# Chip_Socket_Programmer-X01.net
KiCad netlist of a schematic drawn in Altium Designer
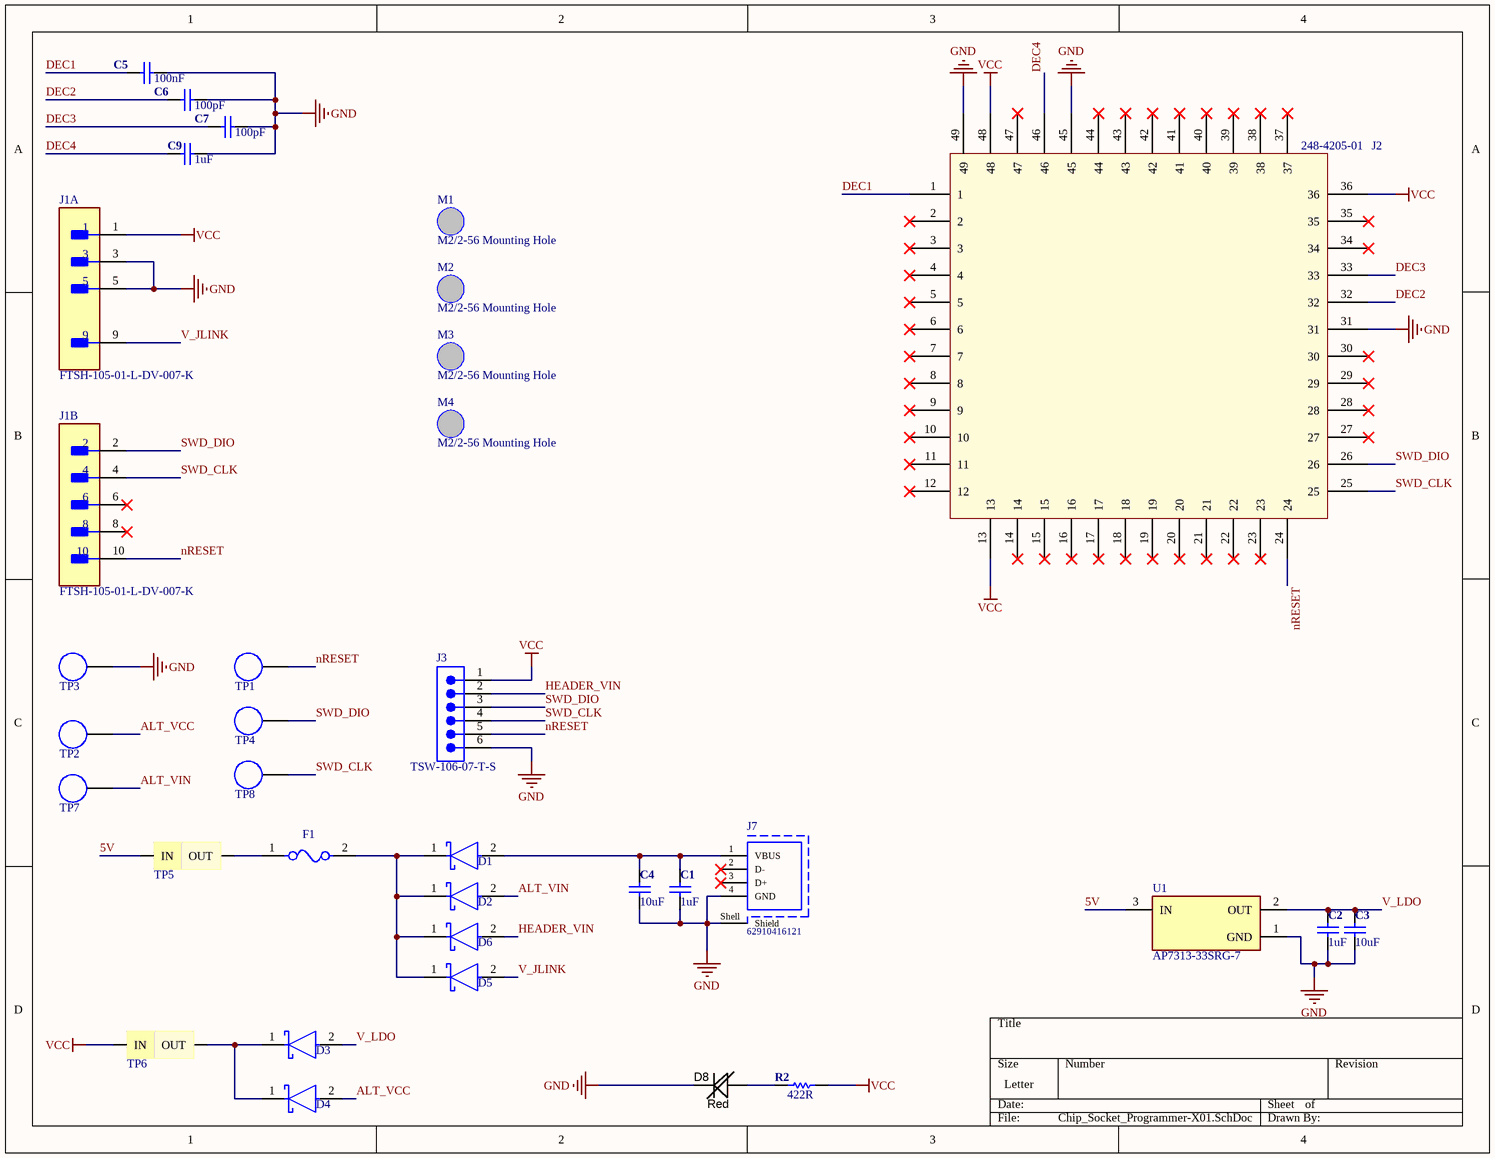
[diagram p0: Chip_Socket_Programmer-X01.SchDoc]

(export (version "E")
  (design (tool "Eeschema 10.0.6"))
  (components
    (comp (ref "C1")
      (value "1uF")
      (footprint "C0402")
      (fields
        (field (name "MANUFACTURER") "Yageo")
        (field (name "MANUFACTURER PART NUMBER") "CC0402MRX5R5BB105")
        (field (name "TOLERANCE") "20%")
      )
      (libsource (lib "DB-X01") (part "C-0402(1005)"))
    )
    (comp (ref "C2")
      (value "1uF")
      (footprint "C0402")
      (fields
        (field (name "MANUFACTURER") "Yageo")
        (field (name "MANUFACTURER PART NUMBER") "CC0402MRX5R5BB105")
        (field (name "TOLERANCE") "20%")
      )
      (libsource (lib "Chip_Socket_Programmer-X01") (part "C-0402(1005)"))
    )
    (comp (ref "C3")
      (value "10uF")
      (footprint "C0402")
      (fields
        (field (name "MANUFACTURER") "Kyocera AVX")
        (field (name "MANUFACTURER PART NUMBER") "0402ZD106MAT2A")
      )
      (libsource (lib "Chip_Socket_Programmer-X01") (part "C-0402(1005)"))
    )
    (comp (ref "C4")
      (value "10uF")
      (footprint "C0402")
      (fields
        (field (name "MANUFACTURER") "Kyocera AVX")
        (field (name "MANUFACTURER PART NUMBER") "0402ZD106MAT2A")
      )
      (libsource (lib "Chip_Socket_Programmer-X01") (part "C-0402(1005)"))
    )
    (comp (ref "C5")
      (value "100nF")
      (footprint "C0402")
      (fields
        (field (name "MANUFACTURER") "Taiyo Yuden")
        (field (name "MANUFACTURER PART NUMBER") "TMK105BJ104KV-F")
        (field (name "TOLERANCE") "10%")
      )
      (libsource (lib "Chip_Socket_Programmer-X01") (part "C-0402(1005)"))
    )
    (comp (ref "C6")
      (value "100pF")
      (footprint "C0402")
      (fields
        (field (name "MANUFACTURER") "Yageo")
        (field (name "MANUFACTURER PART NUMBER") "CC0402FRNPO9BN101")
        (field (name "TOLERANCE") "1%")
      )
      (libsource (lib "Chip_Socket_Programmer-X01") (part "C-0402(1005)"))
    )
    (comp (ref "C7")
      (value "100pF")
      (footprint "C0402")
      (fields
        (field (name "MANUFACTURER") "Yageo")
        (field (name "MANUFACTURER PART NUMBER") "CC0402FRNPO9BN101")
        (field (name "TOLERANCE") "1%")
      )
      (libsource (lib "Chip_Socket_Programmer-X01") (part "C-0402(1005)"))
    )
    (comp (ref "C9")
      (value "1uF")
      (footprint "C0402")
      (fields
        (field (name "MANUFACTURER") "Yageo")
        (field (name "MANUFACTURER PART NUMBER") "CC0402MRX5R5BB105")
        (field (name "TOLERANCE") "20%")
      )
      (libsource (lib "Chip_Socket_Programmer-X01") (part "C-0402(1005)"))
    )
    (comp (ref "D1")
      (value "BAS140WE6327HTSA1")
      (footprint "FP-PG-SOD323-2-MFG")
      (description "DIODE SCHOTTKY 40V 120MA SOD323")
      (fields (field (name "MANUFACTURER") "Infineon"))
      (libsource (lib "Altium Content Vault") (part "1d6ec82d83fb6aee721767c19dac4b9"))
    )
    (comp (ref "D2")
      (value "BAS140WE6327HTSA1")
      (footprint "FP-PG-SOD323-2-MFG")
      (description "DIODE SCHOTTKY 40V 120MA SOD323")
      (fields (field (name "MANUFACTURER") "Infineon"))
      (libsource (lib "Altium Content Vault") (part "1d6ec82d83fb6aee721767c19dac4b9"))
    )
    (comp (ref "D3")
      (value "BAS140WE6327HTSA1")
      (footprint "FP-PG-SOD323-2-MFG")
      (description "DIODE SCHOTTKY 40V 120MA SOD323")
      (fields (field (name "MANUFACTURER") "Infineon"))
      (libsource (lib "Altium Content Vault") (part "1d6ec82d83fb6aee721767c19dac4b9"))
    )
    (comp (ref "D4")
      (value "BAS140WE6327HTSA1")
      (footprint "FP-PG-SOD323-2-MFG")
      (description "DIODE SCHOTTKY 40V 120MA SOD323")
      (fields (field (name "MANUFACTURER") "Infineon"))
      (libsource (lib "Altium Content Vault") (part "1d6ec82d83fb6aee721767c19dac4b9"))
    )
    (comp (ref "D5")
      (value "BAS140WE6327HTSA1")
      (footprint "FP-PG-SOD323-2-MFG")
      (description "DIODE SCHOTTKY 40V 120MA SOD323")
      (fields (field (name "MANUFACTURER") "Infineon"))
      (libsource (lib "Altium Content Vault") (part "1d6ec82d83fb6aee721767c19dac4b9"))
    )
    (comp (ref "D6")
      (value "BAS140WE6327HTSA1")
      (footprint "FP-PG-SOD323-2-MFG")
      (description "DIODE SCHOTTKY 40V 120MA SOD323")
      (fields (field (name "MANUFACTURER") "Infineon"))
      (libsource (lib "Altium Content Vault") (part "1d6ec82d83fb6aee721767c19dac4b9"))
    )
    (comp (ref "D8")
      (value "Red")
      (footprint "LED_0402")
      (description "Single Color LED, Hyper Red, Water Clear, 0.8mm")
      (fields
        (field (name "MANUFACTURER") "Kingbright")
        (field (name "MANUFACTURER PART NUMBER") "APHHS1005SURCK")
      )
      (libsource (lib "Chip_Socket_Programmer-X01") (part "LED_0402(1005)"))
    )
    (comp (ref "F1")
      (value "F0402G0R05FNTR")
      (footprint "FP-F0402G-MFG")
      (description "FUSE BOARD MOUNT 50MA 32VDC 0402")
      (fields
        (field (name "MANUFACTURER") "AVX Corporation")
        (field (name "OCTOPART") "https://octopart.com/f0402g0r05fntr-avx-19631750")
      )
      (libsource (lib "Altium Content Vault") (part "5bcf9b9f640e542cf0359d10258e979"))
    )
    (comp (ref "J1")
      (value "FTSH-105-01-L-DV-007-K")
      (footprint "FTSH-105-01-L-DV-007-K")
      (description "CONN HEADER SMD 10POS 1.27MM")
      (fields (field (name "MANUFACTURER") "Samtec"))
      (libsource (lib "DB-X01") (part "7c368be3265735b2816d0cab4417f87"))
    )
    (comp (ref "J2")
      (value "248-4205-01")
      (footprint "248-4205-01")
      (description "IC Socket")
      (fields (field (name "MANUFACTURER") "3M"))
      (libsource (lib "Chip_Socket_Programmer-X01") (part "248-4205-01"))
    )
    (comp (ref "J3")
      (value "TSW-106-07-T-S")
      (footprint "SMTC-TSW-106-07-X-S")
      (description "0.025\" SQ Post Header, Through-hole, Vertical, -55 to 105 degC, 2.54 mm Pitch, 6-Pin, Male, RoHS")
      (fields (field (name "MANUFACTURER") "Samtec"))
      (libsource (lib "Chip_Socket_Programmer-X01") (part "CMP-1024-00384-1"))
    )
    (comp (ref "J7")
      (value "62910416121")
      (footprint "62910416121")
      (description "USB 2.0 Type B Receptacle WR-COM, Horizontal, SMT, with Pads and Pegs")
      (fields (field (name "MANUFACTURER") "Wurth Electronics"))
      (libsource (lib "Altium Content Vault") (part "WE-USB-4-1SHLD"))
    )
    (comp (ref "M1")
      (value "M2/2-56 Mounting Hole")
      (footprint "Mounting Hole")
      (libsource (lib "Chip_Socket_Programmer-X01") (part "M2/2-56 Mounting Hole"))
    )
    (comp (ref "M2")
      (value "M2/2-56 Mounting Hole")
      (footprint "Mounting Hole")
      (libsource (lib "Chip_Socket_Programmer-X01") (part "M2/2-56 Mounting Hole"))
    )
    (comp (ref "M3")
      (value "M2/2-56 Mounting Hole")
      (footprint "Mounting Hole")
      (libsource (lib "Chip_Socket_Programmer-X01") (part "M2/2-56 Mounting Hole"))
    )
    (comp (ref "M4")
      (value "M2/2-56 Mounting Hole")
      (footprint "Mounting Hole")
      (libsource (lib "Chip_Socket_Programmer-X01") (part "M2/2-56 Mounting Hole"))
    )
    (comp (ref "R2")
      (value "422R")
      (footprint "R0402")
      (description "Fixed Resistor, Thin Film, 0.0625W, 422ohm, 50V, 0.1% +/-Tol, 25ppm/Cel, Surface Mount, 0402")
      (fields
        (field (name "MANUFACTURER") "Yageo")
        (field (name "MANUFACTURER PART NUMBER") "RT0402BRD07422RL")
      )
      (libsource (lib "Chip_Socket_Programmer-X01") (part "R-0402(1005)"))
    )
    (comp (ref "TP1")
      (value "S1751-46R")
      (footprint "S1751-46R")
      (description "PC TEST POINT TIN SMD")
      (fields (field (name "MANUFACTURER") "Harwin Inc."))
      (libsource (lib "Chip_Socket_Programmer-X01") (part "S1751-46R"))
    )
    (comp (ref "TP2")
      (value "S1751-46R")
      (footprint "S1751-46R")
      (description "PC TEST POINT TIN SMD")
      (fields (field (name "MANUFACTURER") "Harwin Inc."))
      (libsource (lib "Chip_Socket_Programmer-X01") (part "S1751-46R"))
    )
    (comp (ref "TP3")
      (value "S1751-46R")
      (footprint "S1751-46R")
      (description "PC TEST POINT TIN SMD")
      (fields (field (name "MANUFACTURER") "Harwin Inc."))
      (libsource (lib "Chip_Socket_Programmer-X01") (part "S1751-46R"))
    )
    (comp (ref "TP4")
      (value "S1751-46R")
      (footprint "S1751-46R")
      (description "PC TEST POINT TIN SMD")
      (fields (field (name "MANUFACTURER") "Harwin Inc."))
      (libsource (lib "Chip_Socket_Programmer-X01") (part "S1751-46R"))
    )
    (comp (ref "TP5")
      (value "JUMPER")
      (footprint "JUMPER")
      (description "SHUNT LP W/HANDLE 2 POS 30AU")
      (fields
        (field (name "MANUFACTURER") "TE Connectivity")
        (field (name "MANUFACTURER PART NUMBER") "8815452")
      )
      (libsource (lib "DB-X01") (part "JUMPER"))
    )
    (comp (ref "TP6")
      (value "JUMPER")
      (footprint "JUMPER")
      (description "SHUNT LP W/HANDLE 2 POS 30AU")
      (fields
        (field (name "MANUFACTURER") "TE Connectivity")
        (field (name "MANUFACTURER PART NUMBER") "8815452")
      )
      (libsource (lib "DB-X02") (part "JUMPER"))
    )
    (comp (ref "TP7")
      (value "S1751-46R")
      (footprint "S1751-46R")
      (description "PC TEST POINT TIN SMD")
      (fields (field (name "MANUFACTURER") "Harwin Inc."))
      (libsource (lib "Chip_Socket_Programmer-X01") (part "S1751-46R"))
    )
    (comp (ref "TP8")
      (value "S1751-46R")
      (footprint "S1751-46R")
      (description "PC TEST POINT TIN SMD")
      (fields (field (name "MANUFACTURER") "Harwin Inc."))
      (libsource (lib "Chip_Socket_Programmer-X01") (part "S1751-46R"))
    )
    (comp (ref "U1")
      (value "AP7313-33SRG-7")
      (footprint "FP-SOT23-IPC_A")
      (description "IC REG LIN 3.3V 150MA SOT23R-3")
      (fields (field (name "MANUFACTURER") "Diodes"))
      (libsource (lib "Altium Content Vault") (part "626efb30cf2a85b0754f90ef0379509"))
    )
  )
  (nets
    (net (code "1") (name "/5V") (class "Default")
      (node (ref "TP5") (pin "1") (pinfunction "IN_1") (pintype "passive"))
      (node (ref "U1") (pin "3") (pinfunction "IN_3") (pintype "passive"))
    )
    (net (code "2") (name "/ALT_VCC") (class "Default")
      (node (ref "D4") (pin "2") (pinfunction "A_2") (pintype "passive"))
      (node (ref "TP2") (pin "1") (pinfunction "1_1") (pintype "passive"))
    )
    (net (code "3") (name "/ALT_VIN") (class "Default")
      (node (ref "D2") (pin "2") (pinfunction "A_2") (pintype "passive"))
      (node (ref "TP7") (pin "1") (pinfunction "1_1") (pintype "passive"))
    )
    (net (code "4") (name "/DEC1") (class "Default")
      (node (ref "C5") (pin "1") (pinfunction "1_1") (pintype "passive"))
      (node (ref "J2") (pin "1") (pinfunction "1_1") (pintype "passive"))
    )
    (net (code "5") (name "/DEC2") (class "Default")
      (node (ref "C6") (pin "1") (pinfunction "1_1") (pintype "passive"))
      (node (ref "J2") (pin "32") (pinfunction "32_32") (pintype "passive"))
    )
    (net (code "6") (name "/DEC3") (class "Default")
      (node (ref "C7") (pin "1") (pinfunction "1_1") (pintype "passive"))
      (node (ref "J2") (pin "33") (pinfunction "33_33") (pintype "passive"))
    )
    (net (code "7") (name "/DEC4") (class "Default")
      (node (ref "C9") (pin "2") (pinfunction "2_2") (pintype "passive"))
      (node (ref "J2") (pin "46") (pinfunction "46_46") (pintype "passive"))
    )
    (net (code "8") (name "/HEADER_VIN") (class "Default")
      (node (ref "D6") (pin "2") (pinfunction "A_2") (pintype "passive"))
      (node (ref "J3") (pin "2") (pinfunction "2_2") (pintype "passive"))
    )
    (net (code "9") (name "/SWD_CLK") (class "Default")
      (node (ref "J1") (pin "4") (pinfunction "4_4") (pintype "passive"))
      (node (ref "J2") (pin "25") (pinfunction "25_25") (pintype "passive"))
      (node (ref "J3") (pin "4") (pinfunction "4_4") (pintype "passive"))
      (node (ref "TP8") (pin "1") (pinfunction "1_1") (pintype "passive"))
    )
    (net (code "10") (name "/SWD_DIO") (class "Default")
      (node (ref "J1") (pin "2") (pinfunction "2_2") (pintype "passive"))
      (node (ref "J2") (pin "26") (pinfunction "26_26") (pintype "passive"))
      (node (ref "J3") (pin "3") (pinfunction "3_3") (pintype "passive"))
      (node (ref "TP4") (pin "1") (pinfunction "1_1") (pintype "passive"))
    )
    (net (code "11") (name "/V_JLINK") (class "Default")
      (node (ref "D5") (pin "2") (pinfunction "A_2") (pintype "passive"))
      (node (ref "J1") (pin "9") (pinfunction "9_9") (pintype "passive"))
    )
    (net (code "12") (name "/V_LDO") (class "Default")
      (node (ref "C2") (pin "1") (pinfunction "1_1") (pintype "passive"))
      (node (ref "C3") (pin "1") (pinfunction "1_1") (pintype "passive"))
      (node (ref "D3") (pin "2") (pinfunction "A_2") (pintype "passive"))
      (node (ref "U1") (pin "2") (pinfunction "OUT_2") (pintype "passive"))
    )
    (net (code "13") (name "/nRESET") (class "Default")
      (node (ref "J1") (pin "10") (pinfunction "10_10") (pintype "passive"))
      (node (ref "J2") (pin "24") (pinfunction "24_24") (pintype "passive"))
      (node (ref "J3") (pin "5") (pinfunction "5_5") (pintype "passive"))
      (node (ref "TP1") (pin "1") (pinfunction "1_1") (pintype "passive"))
    )
    (net (code "14") (name "GND") (class "Default")
      (node (ref "C1") (pin "2") (pinfunction "2_2") (pintype "passive"))
      (node (ref "C2") (pin "2") (pinfunction "2_2") (pintype "passive"))
      (node (ref "C3") (pin "2") (pinfunction "2_2") (pintype "passive"))
      (node (ref "C4") (pin "2") (pinfunction "2_2") (pintype "passive"))
      (node (ref "C5") (pin "2") (pinfunction "2_2") (pintype "passive"))
      (node (ref "C6") (pin "2") (pinfunction "2_2") (pintype "passive"))
      (node (ref "C7") (pin "2") (pinfunction "2_2") (pintype "passive"))
      (node (ref "C9") (pin "1") (pinfunction "1_1") (pintype "passive"))
      (node (ref "D8") (pin "K") (pinfunction "K_K") (pintype "passive"))
      (node (ref "J1") (pin "3") (pinfunction "3_3") (pintype "passive"))
      (node (ref "J1") (pin "5") (pinfunction "5_5") (pintype "passive"))
      (node (ref "J2") (pin "31") (pinfunction "31_31") (pintype "passive"))
      (node (ref "J2") (pin "45") (pinfunction "45_45") (pintype "passive"))
      (node (ref "J2") (pin "49") (pinfunction "49_49") (pintype "passive"))
      (node (ref "J3") (pin "6") (pinfunction "6_6") (pintype "passive"))
      (node (ref "J7") (pin "4") (pinfunction "GND_4") (pintype "passive"))
      (node (ref "J7") (pin "Shell") (pinfunction "Shield_Shell") (pintype "passive"))
      (node (ref "TP3") (pin "1") (pinfunction "1_1") (pintype "passive"))
      (node (ref "U1") (pin "1") (pinfunction "GND_1") (pintype "passive"))
    )
    (net (code "15") (name "Net-(D1-A)") (class "Default")
      (node (ref "C1") (pin "1") (pinfunction "1_1") (pintype "passive"))
      (node (ref "C4") (pin "1") (pinfunction "1_1") (pintype "passive"))
      (node (ref "D1") (pin "2") (pinfunction "A_2") (pintype "passive"))
      (node (ref "J7") (pin "1") (pinfunction "VBUS_1") (pintype "passive"))
    )
    (net (code "16") (name "Net-(D1-C)") (class "Default")
      (node (ref "D1") (pin "1") (pinfunction "C_1") (pintype "passive"))
      (node (ref "D2") (pin "1") (pinfunction "C_1") (pintype "passive"))
      (node (ref "D5") (pin "1") (pinfunction "C_1") (pintype "passive"))
      (node (ref "D6") (pin "1") (pinfunction "C_1") (pintype "passive"))
      (node (ref "F1") (pin "2") (pinfunction "2_2") (pintype "passive"))
    )
    (net (code "17") (name "Net-(D3-C)") (class "Default")
      (node (ref "D3") (pin "1") (pinfunction "C_1") (pintype "passive"))
      (node (ref "D4") (pin "1") (pinfunction "C_1") (pintype "passive"))
      (node (ref "TP6") (pin "2") (pinfunction "OUT_2") (pintype "passive"))
    )
    (net (code "18") (name "Net-(D8-PadA)") (class "Default")
      (node (ref "D8") (pin "A") (pinfunction "A_A") (pintype "passive"))
      (node (ref "R2") (pin "2") (pinfunction "2_2") (pintype "passive"))
    )
    (net (code "19") (name "Net-(TP5-OUT)") (class "Default")
      (node (ref "F1") (pin "1") (pinfunction "1_1") (pintype "passive"))
      (node (ref "TP5") (pin "2") (pinfunction "OUT_2") (pintype "passive"))
    )
    (net (code "20") (name "VCC") (class "Default")
      (node (ref "J1") (pin "1") (pinfunction "1_1") (pintype "passive"))
      (node (ref "J2") (pin "13") (pinfunction "13_13") (pintype "passive"))
      (node (ref "J2") (pin "36") (pinfunction "36_36") (pintype "passive"))
      (node (ref "J2") (pin "48") (pinfunction "48_48") (pintype "passive"))
      (node (ref "J3") (pin "1") (pinfunction "1_1") (pintype "passive"))
      (node (ref "R2") (pin "1") (pinfunction "1_1") (pintype "passive"))
      (node (ref "TP6") (pin "1") (pinfunction "IN_1") (pintype "passive"))
    )
    (net (code "21") (name "unconnected-(J1-Pad6)") (class "Default")
      (node (ref "J1") (pin "6") (pinfunction "6_6") (pintype "passive+no_connect"))
    )
    (net (code "22") (name "unconnected-(J1-Pad8)") (class "Default")
      (node (ref "J1") (pin "8") (pinfunction "8_8") (pintype "passive+no_connect"))
    )
    (net (code "23") (name "unconnected-(J2-Pad2)") (class "Default")
      (node (ref "J2") (pin "2") (pinfunction "2_2") (pintype "passive+no_connect"))
    )
    (net (code "24") (name "unconnected-(J2-Pad3)") (class "Default")
      (node (ref "J2") (pin "3") (pinfunction "3_3") (pintype "passive+no_connect"))
    )
    (net (code "25") (name "unconnected-(J2-Pad4)") (class "Default")
      (node (ref "J2") (pin "4") (pinfunction "4_4") (pintype "passive+no_connect"))
    )
    (net (code "26") (name "unconnected-(J2-Pad5)") (class "Default")
      (node (ref "J2") (pin "5") (pinfunction "5_5") (pintype "passive+no_connect"))
    )
    (net (code "27") (name "unconnected-(J2-Pad6)") (class "Default")
      (node (ref "J2") (pin "6") (pinfunction "6_6") (pintype "passive+no_connect"))
    )
    (net (code "28") (name "unconnected-(J2-Pad7)") (class "Default")
      (node (ref "J2") (pin "7") (pinfunction "7_7") (pintype "passive+no_connect"))
    )
    (net (code "29") (name "unconnected-(J2-Pad8)") (class "Default")
      (node (ref "J2") (pin "8") (pinfunction "8_8") (pintype "passive+no_connect"))
    )
    (net (code "30") (name "unconnected-(J2-Pad9)") (class "Default")
      (node (ref "J2") (pin "9") (pinfunction "9_9") (pintype "passive+no_connect"))
    )
    (net (code "31") (name "unconnected-(J2-Pad10)") (class "Default")
      (node (ref "J2") (pin "10") (pinfunction "10_10") (pintype "passive+no_connect"))
    )
    (net (code "32") (name "unconnected-(J2-Pad11)") (class "Default")
      (node (ref "J2") (pin "11") (pinfunction "11_11") (pintype "passive+no_connect"))
    )
    (net (code "33") (name "unconnected-(J2-Pad12)") (class "Default")
      (node (ref "J2") (pin "12") (pinfunction "12_12") (pintype "passive+no_connect"))
    )
    (net (code "34") (name "unconnected-(J2-Pad14)") (class "Default")
      (node (ref "J2") (pin "14") (pinfunction "14_14") (pintype "passive+no_connect"))
    )
    (net (code "35") (name "unconnected-(J2-Pad15)") (class "Default")
      (node (ref "J2") (pin "15") (pinfunction "15_15") (pintype "passive+no_connect"))
    )
    (net (code "36") (name "unconnected-(J2-Pad16)") (class "Default")
      (node (ref "J2") (pin "16") (pinfunction "16_16") (pintype "passive+no_connect"))
    )
    (net (code "37") (name "unconnected-(J2-Pad17)") (class "Default")
      (node (ref "J2") (pin "17") (pinfunction "17_17") (pintype "passive+no_connect"))
    )
    (net (code "38") (name "unconnected-(J2-Pad18)") (class "Default")
      (node (ref "J2") (pin "18") (pinfunction "18_18") (pintype "passive+no_connect"))
    )
    (net (code "39") (name "unconnected-(J2-Pad19)") (class "Default")
      (node (ref "J2") (pin "19") (pinfunction "19_19") (pintype "passive+no_connect"))
    )
    (net (code "40") (name "unconnected-(J2-Pad20)") (class "Default")
      (node (ref "J2") (pin "20") (pinfunction "20_20") (pintype "passive+no_connect"))
    )
    (net (code "41") (name "unconnected-(J2-Pad21)") (class "Default")
      (node (ref "J2") (pin "21") (pinfunction "21_21") (pintype "passive+no_connect"))
    )
    (net (code "42") (name "unconnected-(J2-Pad22)") (class "Default")
      (node (ref "J2") (pin "22") (pinfunction "22_22") (pintype "passive+no_connect"))
    )
    (net (code "43") (name "unconnected-(J2-Pad23)") (class "Default")
      (node (ref "J2") (pin "23") (pinfunction "23_23") (pintype "passive+no_connect"))
    )
    (net (code "44") (name "unconnected-(J2-Pad27)") (class "Default")
      (node (ref "J2") (pin "27") (pinfunction "27_27") (pintype "passive+no_connect"))
    )
    (net (code "45") (name "unconnected-(J2-Pad28)") (class "Default")
      (node (ref "J2") (pin "28") (pinfunction "28_28") (pintype "passive+no_connect"))
    )
    (net (code "46") (name "unconnected-(J2-Pad29)") (class "Default")
      (node (ref "J2") (pin "29") (pinfunction "29_29") (pintype "passive+no_connect"))
    )
    (net (code "47") (name "unconnected-(J2-Pad30)") (class "Default")
      (node (ref "J2") (pin "30") (pinfunction "30_30") (pintype "passive+no_connect"))
    )
    (net (code "48") (name "unconnected-(J2-Pad34)") (class "Default")
      (node (ref "J2") (pin "34") (pinfunction "34_34") (pintype "passive+no_connect"))
    )
    (net (code "49") (name "unconnected-(J2-Pad35)") (class "Default")
      (node (ref "J2") (pin "35") (pinfunction "35_35") (pintype "passive+no_connect"))
    )
    (net (code "50") (name "unconnected-(J2-Pad37)") (class "Default")
      (node (ref "J2") (pin "37") (pinfunction "37_37") (pintype "passive+no_connect"))
    )
    (net (code "51") (name "unconnected-(J2-Pad38)") (class "Default")
      (node (ref "J2") (pin "38") (pinfunction "38_38") (pintype "passive+no_connect"))
    )
    (net (code "52") (name "unconnected-(J2-Pad39)") (class "Default")
      (node (ref "J2") (pin "39") (pinfunction "39_39") (pintype "passive+no_connect"))
    )
    (net (code "53") (name "unconnected-(J2-Pad40)") (class "Default")
      (node (ref "J2") (pin "40") (pinfunction "40_40") (pintype "passive+no_connect"))
    )
    (net (code "54") (name "unconnected-(J2-Pad41)") (class "Default")
      (node (ref "J2") (pin "41") (pinfunction "41_41") (pintype "passive+no_connect"))
    )
    (net (code "55") (name "unconnected-(J2-Pad42)") (class "Default")
      (node (ref "J2") (pin "42") (pinfunction "42_42") (pintype "passive+no_connect"))
    )
    (net (code "56") (name "unconnected-(J2-Pad43)") (class "Default")
      (node (ref "J2") (pin "43") (pinfunction "43_43") (pintype "passive+no_connect"))
    )
    (net (code "57") (name "unconnected-(J2-Pad44)") (class "Default")
      (node (ref "J2") (pin "44") (pinfunction "44_44") (pintype "passive+no_connect"))
    )
    (net (code "58") (name "unconnected-(J2-Pad47)") (class "Default")
      (node (ref "J2") (pin "47") (pinfunction "47_47") (pintype "passive+no_connect"))
    )
    (net (code "59") (name "unconnected-(J7-D+-Pad3)") (class "Default")
      (node (ref "J7") (pin "3") (pinfunction "D+_3") (pintype "passive+no_connect"))
    )
    (net (code "60") (name "unconnected-(J7-D--Pad2)") (class "Default")
      (node (ref "J7") (pin "2") (pinfunction "D-_2") (pintype "passive+no_connect"))
    )
  )
)
